# PI_DI_Input.net
KiCad netlist of a schematic drawn in Altium Designer
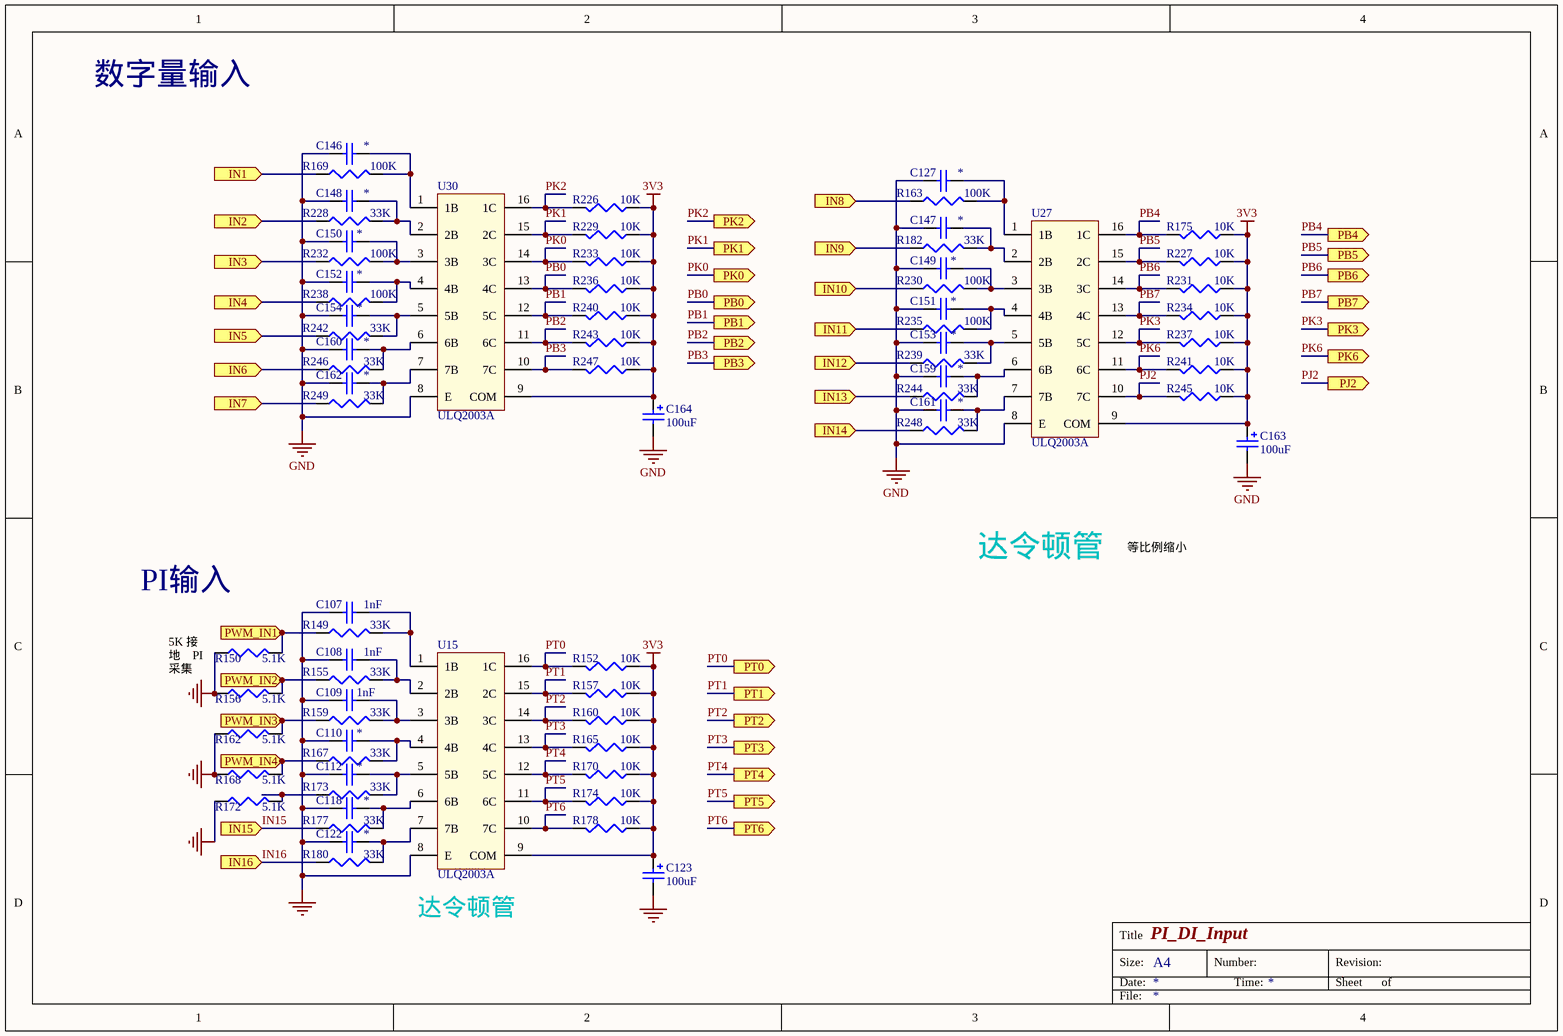
[diagram p0: PI_DI_Input.SchDoc]

(export (version "E")
  (design (tool "Eeschema 10.0.6"))
  (components
    (comp (ref "C107")
      (value "1nF")
      (footprint "0603-L")
      (description "Capacitor")
      (fields (field (name "Comment") "Cap") (field (name "PUBLISHER") "Altium Limited"))
      (libsource (lib "Miscellaneous Devices") (part "Cap"))
    )
    (comp (ref "C108")
      (value "1nF")
      (footprint "0603-L")
      (description "Capacitor")
      (fields (field (name "Comment") "Cap") (field (name "PUBLISHER") "Altium Limited"))
      (libsource (lib "Miscellaneous Devices") (part "Cap"))
    )
    (comp (ref "C109")
      (value "1nF")
      (footprint "0603-L")
      (description "Capacitor")
      (fields (field (name "Comment") "Cap") (field (name "PUBLISHER") "Altium Limited"))
      (libsource (lib "Miscellaneous Devices") (part "Cap"))
    )
    (comp (ref "C110")
      (value "Cap")
      (footprint "0603-L")
      (description "Capacitor")
      (fields (field (name "ALTIUM_VALUE") "*") (field (name "PUBLISHER") "Altium Limited"))
      (libsource (lib "Miscellaneous Devices") (part "Cap"))
    )
    (comp (ref "C112")
      (value "Cap")
      (footprint "0603-L")
      (description "Capacitor")
      (fields (field (name "ALTIUM_VALUE") "*") (field (name "PUBLISHER") "Altium Limited"))
      (libsource (lib "Miscellaneous Devices") (part "Cap"))
    )
    (comp (ref "C118")
      (value "Cap")
      (footprint "0603-L")
      (description "Capacitor")
      (fields (field (name "ALTIUM_VALUE") "*") (field (name "PUBLISHER") "Altium Limited"))
      (libsource (lib "Miscellaneous Devices") (part "Cap"))
    )
    (comp (ref "C122")
      (value "Cap")
      (footprint "0603-L")
      (description "Capacitor")
      (fields (field (name "ALTIUM_VALUE") "*") (field (name "PUBLISHER") "Altium Limited"))
      (libsource (lib "Miscellaneous Devices") (part "Cap"))
    )
    (comp (ref "C123")
      (value "100uF")
      (footprint "CAP1+")
      (description "Polarized Capacitor (Axial)")
      (fields (field (name "Comment") "Cap Pol2") (field (name "PUBLISHER") "Altium Limited"))
      (libsource (lib "Miscellaneous Devices") (part "Cap Pol2"))
    )
    (comp (ref "C127")
      (value "Cap")
      (footprint "0603-L")
      (description "Capacitor")
      (fields (field (name "ALTIUM_VALUE") "*") (field (name "PUBLISHER") "Altium Limited"))
      (libsource (lib "Miscellaneous Devices") (part "Cap"))
    )
    (comp (ref "C146")
      (value "Cap")
      (footprint "0603-L")
      (description "Capacitor")
      (fields (field (name "ALTIUM_VALUE") "*") (field (name "PUBLISHER") "Altium Limited"))
      (libsource (lib "Miscellaneous Devices") (part "Cap"))
    )
    (comp (ref "C147")
      (value "Cap")
      (footprint "0603-L")
      (description "Capacitor")
      (fields (field (name "ALTIUM_VALUE") "*") (field (name "PUBLISHER") "Altium Limited"))
      (libsource (lib "Miscellaneous Devices") (part "Cap"))
    )
    (comp (ref "C148")
      (value "Cap")
      (footprint "0603-L")
      (description "Capacitor")
      (fields (field (name "ALTIUM_VALUE") "*") (field (name "PUBLISHER") "Altium Limited"))
      (libsource (lib "Miscellaneous Devices") (part "Cap"))
    )
    (comp (ref "C149")
      (value "Cap")
      (footprint "0603-L")
      (description "Capacitor")
      (fields (field (name "ALTIUM_VALUE") "*") (field (name "PUBLISHER") "Altium Limited"))
      (libsource (lib "Miscellaneous Devices") (part "Cap"))
    )
    (comp (ref "C150")
      (value "Cap")
      (footprint "0603-L")
      (description "Capacitor")
      (fields (field (name "ALTIUM_VALUE") "*") (field (name "PUBLISHER") "Altium Limited"))
      (libsource (lib "Miscellaneous Devices") (part "Cap"))
    )
    (comp (ref "C151")
      (value "Cap")
      (footprint "0603-L")
      (description "Capacitor")
      (fields (field (name "ALTIUM_VALUE") "*") (field (name "PUBLISHER") "Altium Limited"))
      (libsource (lib "Miscellaneous Devices") (part "Cap"))
    )
    (comp (ref "C152")
      (value "Cap")
      (footprint "0603-L")
      (description "Capacitor")
      (fields (field (name "ALTIUM_VALUE") "*") (field (name "PUBLISHER") "Altium Limited"))
      (libsource (lib "Miscellaneous Devices") (part "Cap"))
    )
    (comp (ref "C153")
      (value "Cap")
      (footprint "0603-L")
      (description "Capacitor")
      (fields (field (name "ALTIUM_VALUE") "*") (field (name "PUBLISHER") "Altium Limited"))
      (libsource (lib "Miscellaneous Devices") (part "Cap"))
    )
    (comp (ref "C154")
      (value "Cap")
      (footprint "0603-L")
      (description "Capacitor")
      (fields (field (name "ALTIUM_VALUE") "*") (field (name "PUBLISHER") "Altium Limited"))
      (libsource (lib "Miscellaneous Devices") (part "Cap"))
    )
    (comp (ref "C159")
      (value "Cap")
      (footprint "0603-L")
      (description "Capacitor")
      (fields (field (name "ALTIUM_VALUE") "*") (field (name "PUBLISHER") "Altium Limited"))
      (libsource (lib "Miscellaneous Devices") (part "Cap"))
    )
    (comp (ref "C160")
      (value "Cap")
      (footprint "0603-L")
      (description "Capacitor")
      (fields (field (name "ALTIUM_VALUE") "*") (field (name "PUBLISHER") "Altium Limited"))
      (libsource (lib "Miscellaneous Devices") (part "Cap"))
    )
    (comp (ref "C161")
      (value "Cap")
      (footprint "0603-L")
      (description "Capacitor")
      (fields (field (name "ALTIUM_VALUE") "*") (field (name "PUBLISHER") "Altium Limited"))
      (libsource (lib "Miscellaneous Devices") (part "Cap"))
    )
    (comp (ref "C162")
      (value "Cap")
      (footprint "0603-L")
      (description "Capacitor")
      (fields (field (name "ALTIUM_VALUE") "*") (field (name "PUBLISHER") "Altium Limited"))
      (libsource (lib "Miscellaneous Devices") (part "Cap"))
    )
    (comp (ref "C163")
      (value "100uF")
      (footprint "CAP1+")
      (description "Polarized Capacitor (Axial)")
      (fields (field (name "Comment") "Cap Pol2") (field (name "PUBLISHER") "Altium Limited"))
      (libsource (lib "Miscellaneous Devices") (part "Cap Pol2"))
    )
    (comp (ref "C164")
      (value "100uF")
      (footprint "CAP1+")
      (description "Polarized Capacitor (Axial)")
      (fields (field (name "Comment") "Cap Pol2") (field (name "PUBLISHER") "Altium Limited"))
      (libsource (lib "Miscellaneous Devices") (part "Cap Pol2"))
    )
    (comp (ref "R149")
      (value "33K")
      (footprint "0603-L")
      (description "Resistor")
      (fields (field (name "Comment") "Res3") (field (name "PUBLISHER") "Altium Limited"))
      (libsource (lib "Miscellaneous Devices") (part "Res3"))
    )
    (comp (ref "R150")
      (value "5.1K")
      (footprint "0603-L")
      (description "Resistor")
      (fields (field (name "Comment") "Res3") (field (name "PUBLISHER") "Altium Limited"))
      (libsource (lib "Miscellaneous Devices") (part "Res3"))
    )
    (comp (ref "R152")
      (value "10K")
      (footprint "0603-L")
      (description "Resistor")
      (fields (field (name "Comment") "Res3") (field (name "PUBLISHER") "Altium Limited"))
      (libsource (lib "Miscellaneous Devices") (part "Res3"))
    )
    (comp (ref "R155")
      (value "33K")
      (footprint "0603-L")
      (description "Resistor")
      (fields (field (name "Comment") "Res3") (field (name "PUBLISHER") "Altium Limited"))
      (libsource (lib "Miscellaneous Devices") (part "Res3"))
    )
    (comp (ref "R156")
      (value "5.1K")
      (footprint "0603-L")
      (description "Resistor")
      (fields (field (name "Comment") "Res3") (field (name "PUBLISHER") "Altium Limited"))
      (libsource (lib "Miscellaneous Devices") (part "Res3"))
    )
    (comp (ref "R157")
      (value "10K")
      (footprint "0603-L")
      (description "Resistor")
      (fields (field (name "Comment") "Res3") (field (name "PUBLISHER") "Altium Limited"))
      (libsource (lib "Miscellaneous Devices") (part "Res3"))
    )
    (comp (ref "R159")
      (value "33K")
      (footprint "0603-L")
      (description "Resistor")
      (fields (field (name "Comment") "Res3") (field (name "PUBLISHER") "Altium Limited"))
      (libsource (lib "Miscellaneous Devices") (part "Res3"))
    )
    (comp (ref "R160")
      (value "10K")
      (footprint "0603-L")
      (description "Resistor")
      (fields (field (name "Comment") "Res3") (field (name "PUBLISHER") "Altium Limited"))
      (libsource (lib "Miscellaneous Devices") (part "Res3"))
    )
    (comp (ref "R162")
      (value "5.1K")
      (footprint "0603-L")
      (description "Resistor")
      (fields (field (name "Comment") "Res3") (field (name "PUBLISHER") "Altium Limited"))
      (libsource (lib "Miscellaneous Devices") (part "Res3"))
    )
    (comp (ref "R163")
      (value "100K")
      (footprint "0603-L")
      (description "Resistor")
      (fields (field (name "Comment") "Res3") (field (name "PUBLISHER") "Altium Limited"))
      (libsource (lib "Miscellaneous Devices") (part "Res3"))
    )
    (comp (ref "R165")
      (value "10K")
      (footprint "0603-L")
      (description "Resistor")
      (fields (field (name "Comment") "Res3") (field (name "PUBLISHER") "Altium Limited"))
      (libsource (lib "Miscellaneous Devices") (part "Res3"))
    )
    (comp (ref "R167")
      (value "33K")
      (footprint "0603-L")
      (description "Resistor")
      (fields (field (name "Comment") "Res3") (field (name "PUBLISHER") "Altium Limited"))
      (libsource (lib "Miscellaneous Devices") (part "Res3"))
    )
    (comp (ref "R168")
      (value "5.1K")
      (footprint "0603-L")
      (description "Resistor")
      (fields (field (name "Comment") "Res3") (field (name "PUBLISHER") "Altium Limited"))
      (libsource (lib "Miscellaneous Devices") (part "Res3"))
    )
    (comp (ref "R169")
      (value "100K")
      (footprint "0603-L")
      (description "Resistor")
      (fields (field (name "Comment") "Res3") (field (name "PUBLISHER") "Altium Limited"))
      (libsource (lib "Miscellaneous Devices") (part "Res3"))
    )
    (comp (ref "R170")
      (value "10K")
      (footprint "0603-L")
      (description "Resistor")
      (fields (field (name "Comment") "Res3") (field (name "PUBLISHER") "Altium Limited"))
      (libsource (lib "Miscellaneous Devices") (part "Res3"))
    )
    (comp (ref "R172")
      (value "5.1K")
      (footprint "0603-L")
      (description "Resistor")
      (fields (field (name "Comment") "Res3") (field (name "PUBLISHER") "Altium Limited"))
      (libsource (lib "Miscellaneous Devices") (part "Res3"))
    )
    (comp (ref "R173")
      (value "33K")
      (footprint "0603-L")
      (description "Resistor")
      (fields (field (name "Comment") "Res3") (field (name "PUBLISHER") "Altium Limited"))
      (libsource (lib "Miscellaneous Devices") (part "Res3"))
    )
    (comp (ref "R174")
      (value "10K")
      (footprint "0603-L")
      (description "Resistor")
      (fields (field (name "Comment") "Res3") (field (name "PUBLISHER") "Altium Limited"))
      (libsource (lib "Miscellaneous Devices") (part "Res3"))
    )
    (comp (ref "R175")
      (value "10K")
      (footprint "0603-L")
      (description "Resistor")
      (fields (field (name "Comment") "Res3") (field (name "PUBLISHER") "Altium Limited"))
      (libsource (lib "Miscellaneous Devices") (part "Res3"))
    )
    (comp (ref "R177")
      (value "33K")
      (footprint "0603-L")
      (description "Resistor")
      (fields (field (name "Comment") "Res3") (field (name "PUBLISHER") "Altium Limited"))
      (libsource (lib "Miscellaneous Devices") (part "Res3"))
    )
    (comp (ref "R178")
      (value "10K")
      (footprint "0603-L")
      (description "Resistor")
      (fields (field (name "Comment") "Res3") (field (name "PUBLISHER") "Altium Limited"))
      (libsource (lib "Miscellaneous Devices") (part "Res3"))
    )
    (comp (ref "R180")
      (value "33K")
      (footprint "0603-L")
      (description "Resistor")
      (fields (field (name "Comment") "Res3") (field (name "PUBLISHER") "Altium Limited"))
      (libsource (lib "Miscellaneous Devices") (part "Res3"))
    )
    (comp (ref "R182")
      (value "33K")
      (footprint "0603-L")
      (description "Resistor")
      (fields (field (name "Comment") "Res3") (field (name "PUBLISHER") "Altium Limited"))
      (libsource (lib "Miscellaneous Devices") (part "Res3"))
    )
    (comp (ref "R226")
      (value "10K")
      (footprint "0603-L")
      (description "Resistor")
      (fields (field (name "Comment") "Res3") (field (name "PUBLISHER") "Altium Limited"))
      (libsource (lib "Miscellaneous Devices") (part "Res3"))
    )
    (comp (ref "R227")
      (value "10K")
      (footprint "0603-L")
      (description "Resistor")
      (fields (field (name "Comment") "Res3") (field (name "PUBLISHER") "Altium Limited"))
      (libsource (lib "Miscellaneous Devices") (part "Res3"))
    )
    (comp (ref "R228")
      (value "33K")
      (footprint "0603-L")
      (description "Resistor")
      (fields (field (name "Comment") "Res3") (field (name "PUBLISHER") "Altium Limited"))
      (libsource (lib "Miscellaneous Devices") (part "Res3"))
    )
    (comp (ref "R229")
      (value "10K")
      (footprint "0603-L")
      (description "Resistor")
      (fields (field (name "Comment") "Res3") (field (name "PUBLISHER") "Altium Limited"))
      (libsource (lib "Miscellaneous Devices") (part "Res3"))
    )
    (comp (ref "R230")
      (value "100K")
      (footprint "0603-L")
      (description "Resistor")
      (fields (field (name "Comment") "Res3") (field (name "PUBLISHER") "Altium Limited"))
      (libsource (lib "Miscellaneous Devices") (part "Res3"))
    )
    (comp (ref "R231")
      (value "10K")
      (footprint "0603-L")
      (description "Resistor")
      (fields (field (name "Comment") "Res3") (field (name "PUBLISHER") "Altium Limited"))
      (libsource (lib "Miscellaneous Devices") (part "Res3"))
    )
    (comp (ref "R232")
      (value "100K")
      (footprint "0603-L")
      (description "Resistor")
      (fields (field (name "Comment") "Res3") (field (name "PUBLISHER") "Altium Limited"))
      (libsource (lib "Miscellaneous Devices") (part "Res3"))
    )
    (comp (ref "R233")
      (value "10K")
      (footprint "0603-L")
      (description "Resistor")
      (fields (field (name "Comment") "Res3") (field (name "PUBLISHER") "Altium Limited"))
      (libsource (lib "Miscellaneous Devices") (part "Res3"))
    )
    (comp (ref "R234")
      (value "10K")
      (footprint "0603-L")
      (description "Resistor")
      (fields (field (name "Comment") "Res3") (field (name "PUBLISHER") "Altium Limited"))
      (libsource (lib "Miscellaneous Devices") (part "Res3"))
    )
    (comp (ref "R235")
      (value "100K")
      (footprint "0603-L")
      (description "Resistor")
      (fields (field (name "Comment") "Res3") (field (name "PUBLISHER") "Altium Limited"))
      (libsource (lib "Miscellaneous Devices") (part "Res3"))
    )
    (comp (ref "R236")
      (value "10K")
      (footprint "0603-L")
      (description "Resistor")
      (fields (field (name "Comment") "Res3") (field (name "PUBLISHER") "Altium Limited"))
      (libsource (lib "Miscellaneous Devices") (part "Res3"))
    )
    (comp (ref "R237")
      (value "10K")
      (footprint "0603-L")
      (description "Resistor")
      (fields (field (name "Comment") "Res3") (field (name "PUBLISHER") "Altium Limited"))
      (libsource (lib "Miscellaneous Devices") (part "Res3"))
    )
    (comp (ref "R238")
      (value "100K")
      (footprint "0603-L")
      (description "Resistor")
      (fields (field (name "Comment") "Res3") (field (name "PUBLISHER") "Altium Limited"))
      (libsource (lib "Miscellaneous Devices") (part "Res3"))
    )
    (comp (ref "R239")
      (value "33K")
      (footprint "0603-L")
      (description "Resistor")
      (fields (field (name "Comment") "Res3") (field (name "PUBLISHER") "Altium Limited"))
      (libsource (lib "Miscellaneous Devices") (part "Res3"))
    )
    (comp (ref "R240")
      (value "10K")
      (footprint "0603-L")
      (description "Resistor")
      (fields (field (name "Comment") "Res3") (field (name "PUBLISHER") "Altium Limited"))
      (libsource (lib "Miscellaneous Devices") (part "Res3"))
    )
    (comp (ref "R241")
      (value "10K")
      (footprint "0603-L")
      (description "Resistor")
      (fields (field (name "Comment") "Res3") (field (name "PUBLISHER") "Altium Limited"))
      (libsource (lib "Miscellaneous Devices") (part "Res3"))
    )
    (comp (ref "R242")
      (value "33K")
      (footprint "0603-L")
      (description "Resistor")
      (fields (field (name "Comment") "Res3") (field (name "PUBLISHER") "Altium Limited"))
      (libsource (lib "Miscellaneous Devices") (part "Res3"))
    )
    (comp (ref "R243")
      (value "10K")
      (footprint "0603-L")
      (description "Resistor")
      (fields (field (name "Comment") "Res3") (field (name "PUBLISHER") "Altium Limited"))
      (libsource (lib "Miscellaneous Devices") (part "Res3"))
    )
    (comp (ref "R244")
      (value "33K")
      (footprint "0603-L")
      (description "Resistor")
      (fields (field (name "Comment") "Res3") (field (name "PUBLISHER") "Altium Limited"))
      (libsource (lib "Miscellaneous Devices") (part "Res3"))
    )
    (comp (ref "R245")
      (value "10K")
      (footprint "0603-L")
      (description "Resistor")
      (fields (field (name "Comment") "Res3") (field (name "PUBLISHER") "Altium Limited"))
      (libsource (lib "Miscellaneous Devices") (part "Res3"))
    )
    (comp (ref "R246")
      (value "33K")
      (footprint "0603-L")
      (description "Resistor")
      (fields (field (name "Comment") "Res3") (field (name "PUBLISHER") "Altium Limited"))
      (libsource (lib "Miscellaneous Devices") (part "Res3"))
    )
    (comp (ref "R247")
      (value "10K")
      (footprint "0603-L")
      (description "Resistor")
      (fields (field (name "Comment") "Res3") (field (name "PUBLISHER") "Altium Limited"))
      (libsource (lib "Miscellaneous Devices") (part "Res3"))
    )
    (comp (ref "R248")
      (value "33K")
      (footprint "0603-L")
      (description "Resistor")
      (fields (field (name "Comment") "Res3") (field (name "PUBLISHER") "Altium Limited"))
      (libsource (lib "Miscellaneous Devices") (part "Res3"))
    )
    (comp (ref "R249")
      (value "33K")
      (footprint "0603-L")
      (description "Resistor")
      (fields (field (name "Comment") "Res3") (field (name "PUBLISHER") "Altium Limited"))
      (libsource (lib "Miscellaneous Devices") (part "Res3"))
    )
    (comp (ref "U15") (value "ULQ2003A") (footprint "HC4851") (libsource (lib "整车控制器") (part "ULQ2003A")))
    (comp (ref "U27") (value "ULQ2003A") (footprint "HC4851") (libsource (lib "整车控制器") (part "ULQ2003A")))
    (comp (ref "U30") (value "ULQ2003A") (footprint "HC4851") (libsource (lib "整车控制器") (part "ULQ2003A")))
  )
  (nets
    (net (code "1") (name "/IN1") (class "Default")
      (node (ref "R169") (pin "1") (pinfunction "1_1") (pintype "passive"))
    )
    (net (code "2") (name "/IN2") (class "Default")
      (node (ref "R228") (pin "1") (pinfunction "1_1") (pintype "passive"))
    )
    (net (code "3") (name "/IN3") (class "Default")
      (node (ref "R232") (pin "1") (pinfunction "1_1") (pintype "passive"))
    )
    (net (code "4") (name "/IN4") (class "Default")
      (node (ref "R238") (pin "1") (pinfunction "1_1") (pintype "passive"))
    )
    (net (code "5") (name "/IN5") (class "Default")
      (node (ref "R242") (pin "1") (pinfunction "1_1") (pintype "passive"))
    )
    (net (code "6") (name "/IN6") (class "Default")
      (node (ref "R246") (pin "1") (pinfunction "1_1") (pintype "passive"))
    )
    (net (code "7") (name "/IN7") (class "Default")
      (node (ref "R249") (pin "1") (pinfunction "1_1") (pintype "passive"))
    )
    (net (code "8") (name "/IN8") (class "Default")
      (node (ref "R163") (pin "1") (pinfunction "1_1") (pintype "passive"))
    )
    (net (code "9") (name "/IN9") (class "Default")
      (node (ref "R182") (pin "1") (pinfunction "1_1") (pintype "passive"))
    )
    (net (code "10") (name "/IN10") (class "Default")
      (node (ref "R230") (pin "1") (pinfunction "1_1") (pintype "passive"))
    )
    (net (code "11") (name "/IN11") (class "Default")
      (node (ref "R235") (pin "1") (pinfunction "1_1") (pintype "passive"))
    )
    (net (code "12") (name "/IN12") (class "Default")
      (node (ref "R239") (pin "1") (pinfunction "1_1") (pintype "passive"))
    )
    (net (code "13") (name "/IN13") (class "Default")
      (node (ref "R244") (pin "1") (pinfunction "1_1") (pintype "passive"))
    )
    (net (code "14") (name "/IN14") (class "Default")
      (node (ref "R248") (pin "1") (pinfunction "1_1") (pintype "passive"))
    )
    (net (code "15") (name "/IN15") (class "Default")
      (node (ref "R177") (pin "1") (pinfunction "1_1") (pintype "passive"))
    )
    (net (code "16") (name "/IN16") (class "Default")
      (node (ref "R180") (pin "1") (pinfunction "1_1") (pintype "passive"))
    )
    (net (code "17") (name "/PB0") (class "Default")
      (node (ref "R236") (pin "2") (pinfunction "2_2") (pintype "passive"))
      (node (ref "U30") (pin "13") (pinfunction "4C_13") (pintype "passive"))
    )
    (net (code "18") (name "/PB1") (class "Default")
      (node (ref "R240") (pin "2") (pinfunction "2_2") (pintype "passive"))
      (node (ref "U30") (pin "12") (pinfunction "5C_12") (pintype "passive"))
    )
    (net (code "19") (name "/PB2") (class "Default")
      (node (ref "R243") (pin "2") (pinfunction "2_2") (pintype "passive"))
      (node (ref "U30") (pin "11") (pinfunction "6C_11") (pintype "passive"))
    )
    (net (code "20") (name "/PB3") (class "Default")
      (node (ref "R247") (pin "2") (pinfunction "2_2") (pintype "passive"))
      (node (ref "U30") (pin "10") (pinfunction "7C_10") (pintype "passive"))
    )
    (net (code "21") (name "/PB4") (class "Default")
      (node (ref "R175") (pin "2") (pinfunction "2_2") (pintype "passive"))
      (node (ref "U27") (pin "16") (pinfunction "1C_16") (pintype "passive"))
    )
    (net (code "22") (name "/PB5") (class "Default")
      (node (ref "R227") (pin "2") (pinfunction "2_2") (pintype "passive"))
      (node (ref "U27") (pin "15") (pinfunction "2C_15") (pintype "passive"))
    )
    (net (code "23") (name "/PB6") (class "Default")
      (node (ref "R231") (pin "2") (pinfunction "2_2") (pintype "passive"))
      (node (ref "U27") (pin "14") (pinfunction "3C_14") (pintype "passive"))
    )
    (net (code "24") (name "/PB7") (class "Default")
      (node (ref "R234") (pin "2") (pinfunction "2_2") (pintype "passive"))
      (node (ref "U27") (pin "13") (pinfunction "4C_13") (pintype "passive"))
    )
    (net (code "25") (name "/PJ2") (class "Default")
      (node (ref "R245") (pin "2") (pinfunction "2_2") (pintype "passive"))
      (node (ref "U27") (pin "10") (pinfunction "7C_10") (pintype "passive"))
    )
    (net (code "26") (name "/PK0") (class "Default")
      (node (ref "R233") (pin "2") (pinfunction "2_2") (pintype "passive"))
      (node (ref "U30") (pin "14") (pinfunction "3C_14") (pintype "passive"))
    )
    (net (code "27") (name "/PK1") (class "Default")
      (node (ref "R229") (pin "2") (pinfunction "2_2") (pintype "passive"))
      (node (ref "U30") (pin "15") (pinfunction "2C_15") (pintype "passive"))
    )
    (net (code "28") (name "/PK2") (class "Default")
      (node (ref "R226") (pin "2") (pinfunction "2_2") (pintype "passive"))
      (node (ref "U30") (pin "16") (pinfunction "1C_16") (pintype "passive"))
    )
    (net (code "29") (name "/PK3") (class "Default")
      (node (ref "R237") (pin "2") (pinfunction "2_2") (pintype "passive"))
      (node (ref "U27") (pin "12") (pinfunction "5C_12") (pintype "passive"))
    )
    (net (code "30") (name "/PK6") (class "Default")
      (node (ref "R241") (pin "2") (pinfunction "2_2") (pintype "passive"))
      (node (ref "U27") (pin "11") (pinfunction "6C_11") (pintype "passive"))
    )
    (net (code "31") (name "/PT0") (class "Default")
      (node (ref "R152") (pin "2") (pinfunction "2_2") (pintype "passive"))
      (node (ref "U15") (pin "16") (pinfunction "1C_16") (pintype "passive"))
    )
    (net (code "32") (name "/PT1") (class "Default")
      (node (ref "R157") (pin "2") (pinfunction "2_2") (pintype "passive"))
      (node (ref "U15") (pin "15") (pinfunction "2C_15") (pintype "passive"))
    )
    (net (code "33") (name "/PT2") (class "Default")
      (node (ref "R160") (pin "2") (pinfunction "2_2") (pintype "passive"))
      (node (ref "U15") (pin "14") (pinfunction "3C_14") (pintype "passive"))
    )
    (net (code "34") (name "/PT3") (class "Default")
      (node (ref "R165") (pin "2") (pinfunction "2_2") (pintype "passive"))
      (node (ref "U15") (pin "13") (pinfunction "4C_13") (pintype "passive"))
    )
    (net (code "35") (name "/PT4") (class "Default")
      (node (ref "R170") (pin "2") (pinfunction "2_2") (pintype "passive"))
      (node (ref "U15") (pin "12") (pinfunction "5C_12") (pintype "passive"))
    )
    (net (code "36") (name "/PT5") (class "Default")
      (node (ref "R174") (pin "2") (pinfunction "2_2") (pintype "passive"))
      (node (ref "U15") (pin "11") (pinfunction "6C_11") (pintype "passive"))
    )
    (net (code "37") (name "/PT6") (class "Default")
      (node (ref "R178") (pin "2") (pinfunction "2_2") (pintype "passive"))
      (node (ref "U15") (pin "10") (pinfunction "7C_10") (pintype "passive"))
    )
    (net (code "38") (name "/PWM_IN1") (class "Default")
      (node (ref "R149") (pin "1") (pinfunction "1_1") (pintype "passive"))
      (node (ref "R150") (pin "2") (pinfunction "2_2") (pintype "passive"))
    )
    (net (code "39") (name "/PWM_IN2") (class "Default")
      (node (ref "R155") (pin "1") (pinfunction "1_1") (pintype "passive"))
      (node (ref "R156") (pin "2") (pinfunction "2_2") (pintype "passive"))
    )
    (net (code "40") (name "/PWM_IN3") (class "Default")
      (node (ref "R159") (pin "1") (pinfunction "1_1") (pintype "passive"))
      (node (ref "R162") (pin "2") (pinfunction "2_2") (pintype "passive"))
    )
    (net (code "41") (name "/PWM_IN4") (class "Default")
      (node (ref "R167") (pin "1") (pinfunction "1_1") (pintype "passive"))
      (node (ref "R168") (pin "2") (pinfunction "2_2") (pintype "passive"))
    )
    (net (code "42") (name "3V3") (class "Default")
      (node (ref "C123") (pin "1") (pinfunction "1_1") (pintype "passive"))
      (node (ref "C163") (pin "1") (pinfunction "1_1") (pintype "passive"))
      (node (ref "C164") (pin "1") (pinfunction "1_1") (pintype "passive"))
      (node (ref "R152") (pin "1") (pinfunction "1_1") (pintype "passive"))
      (node (ref "R157") (pin "1") (pinfunction "1_1") (pintype "passive"))
      (node (ref "R160") (pin "1") (pinfunction "1_1") (pintype "passive"))
      (node (ref "R165") (pin "1") (pinfunction "1_1") (pintype "passive"))
      (node (ref "R170") (pin "1") (pinfunction "1_1") (pintype "passive"))
      (node (ref "R174") (pin "1") (pinfunction "1_1") (pintype "passive"))
      (node (ref "R175") (pin "1") (pinfunction "1_1") (pintype "passive"))
      (node (ref "R178") (pin "1") (pinfunction "1_1") (pintype "passive"))
      (node (ref "R226") (pin "1") (pinfunction "1_1") (pintype "passive"))
      (node (ref "R227") (pin "1") (pinfunction "1_1") (pintype "passive"))
      (node (ref "R229") (pin "1") (pinfunction "1_1") (pintype "passive"))
      (node (ref "R231") (pin "1") (pinfunction "1_1") (pintype "passive"))
      (node (ref "R233") (pin "1") (pinfunction "1_1") (pintype "passive"))
      (node (ref "R234") (pin "1") (pinfunction "1_1") (pintype "passive"))
      (node (ref "R236") (pin "1") (pinfunction "1_1") (pintype "passive"))
      (node (ref "R237") (pin "1") (pinfunction "1_1") (pintype "passive"))
      (node (ref "R240") (pin "1") (pinfunction "1_1") (pintype "passive"))
      (node (ref "R241") (pin "1") (pinfunction "1_1") (pintype "passive"))
      (node (ref "R243") (pin "1") (pinfunction "1_1") (pintype "passive"))
      (node (ref "R245") (pin "1") (pinfunction "1_1") (pintype "passive"))
      (node (ref "R247") (pin "1") (pinfunction "1_1") (pintype "passive"))
      (node (ref "U15") (pin "9") (pinfunction "COM_9") (pintype "passive"))
      (node (ref "U27") (pin "9") (pinfunction "COM_9") (pintype "passive"))
      (node (ref "U30") (pin "9") (pinfunction "COM_9") (pintype "passive"))
    )
    (net (code "43") (name "GND") (class "Default")
      (node (ref "C107") (pin "2") (pinfunction "2_2") (pintype "passive"))
      (node (ref "C108") (pin "2") (pinfunction "2_2") (pintype "passive"))
      (node (ref "C109") (pin "2") (pinfunction "2_2") (pintype "passive"))
      (node (ref "C110") (pin "2") (pinfunction "2_2") (pintype "passive"))
      (node (ref "C112") (pin "2") (pinfunction "2_2") (pintype "passive"))
      (node (ref "C118") (pin "2") (pinfunction "2_2") (pintype "passive"))
      (node (ref "C122") (pin "2") (pinfunction "2_2") (pintype "passive"))
      (node (ref "C123") (pin "2") (pinfunction "2_2") (pintype "passive"))
      (node (ref "C127") (pin "2") (pinfunction "2_2") (pintype "passive"))
      (node (ref "C146") (pin "2") (pinfunction "2_2") (pintype "passive"))
      (node (ref "C147") (pin "2") (pinfunction "2_2") (pintype "passive"))
      (node (ref "C148") (pin "2") (pinfunction "2_2") (pintype "passive"))
      (node (ref "C149") (pin "2") (pinfunction "2_2") (pintype "passive"))
      (node (ref "C150") (pin "2") (pinfunction "2_2") (pintype "passive"))
      (node (ref "C151") (pin "2") (pinfunction "2_2") (pintype "passive"))
      (node (ref "C152") (pin "2") (pinfunction "2_2") (pintype "passive"))
      (node (ref "C153") (pin "2") (pinfunction "2_2") (pintype "passive"))
      (node (ref "C154") (pin "2") (pinfunction "2_2") (pintype "passive"))
      (node (ref "C159") (pin "2") (pinfunction "2_2") (pintype "passive"))
      (node (ref "C160") (pin "2") (pinfunction "2_2") (pintype "passive"))
      (node (ref "C161") (pin "2") (pinfunction "2_2") (pintype "passive"))
      (node (ref "C162") (pin "2") (pinfunction "2_2") (pintype "passive"))
      (node (ref "C163") (pin "2") (pinfunction "2_2") (pintype "passive"))
      (node (ref "C164") (pin "2") (pinfunction "2_2") (pintype "passive"))
      (node (ref "R150") (pin "1") (pinfunction "1_1") (pintype "passive"))
      (node (ref "R156") (pin "1") (pinfunction "1_1") (pintype "passive"))
      (node (ref "R162") (pin "1") (pinfunction "1_1") (pintype "passive"))
      (node (ref "R168") (pin "1") (pinfunction "1_1") (pintype "passive"))
      (node (ref "R172") (pin "1") (pinfunction "1_1") (pintype "passive"))
      (node (ref "U15") (pin "8") (pinfunction "E_8") (pintype "passive"))
      (node (ref "U27") (pin "8") (pinfunction "E_8") (pintype "passive"))
      (node (ref "U30") (pin "8") (pinfunction "E_8") (pintype "passive"))
    )
    (net (code "44") (name "Net-(R172-Pad2)") (class "Default")
      (node (ref "R172") (pin "2") (pinfunction "2_2") (pintype "passive"))
      (node (ref "R173") (pin "1") (pinfunction "1_1") (pintype "passive"))
    )
    (net (code "45") (name "Net-(U15-1B)") (class "Default")
      (node (ref "C107") (pin "1") (pinfunction "1_1") (pintype "passive"))
      (node (ref "R149") (pin "2") (pinfunction "2_2") (pintype "passive"))
      (node (ref "U15") (pin "1") (pinfunction "1B_1") (pintype "passive"))
    )
    (net (code "46") (name "Net-(U15-2B)") (class "Default")
      (node (ref "C108") (pin "1") (pinfunction "1_1") (pintype "passive"))
      (node (ref "R155") (pin "2") (pinfunction "2_2") (pintype "passive"))
      (node (ref "U15") (pin "2") (pinfunction "2B_2") (pintype "passive"))
    )
    (net (code "47") (name "Net-(U15-3B)") (class "Default")
      (node (ref "C109") (pin "1") (pinfunction "1_1") (pintype "passive"))
      (node (ref "R159") (pin "2") (pinfunction "2_2") (pintype "passive"))
      (node (ref "U15") (pin "3") (pinfunction "3B_3") (pintype "passive"))
    )
    (net (code "48") (name "Net-(U15-4B)") (class "Default")
      (node (ref "C110") (pin "1") (pinfunction "1_1") (pintype "passive"))
      (node (ref "R167") (pin "2") (pinfunction "2_2") (pintype "passive"))
      (node (ref "U15") (pin "4") (pinfunction "4B_4") (pintype "passive"))
    )
    (net (code "49") (name "Net-(U15-5B)") (class "Default")
      (node (ref "C112") (pin "1") (pinfunction "1_1") (pintype "passive"))
      (node (ref "R173") (pin "2") (pinfunction "2_2") (pintype "passive"))
      (node (ref "U15") (pin "5") (pinfunction "5B_5") (pintype "passive"))
    )
    (net (code "50") (name "Net-(U15-6B)") (class "Default")
      (node (ref "C118") (pin "1") (pinfunction "1_1") (pintype "passive"))
      (node (ref "R177") (pin "2") (pinfunction "2_2") (pintype "passive"))
      (node (ref "U15") (pin "6") (pinfunction "6B_6") (pintype "passive"))
    )
    (net (code "51") (name "Net-(U15-7B)") (class "Default")
      (node (ref "C122") (pin "1") (pinfunction "1_1") (pintype "passive"))
      (node (ref "R180") (pin "2") (pinfunction "2_2") (pintype "passive"))
      (node (ref "U15") (pin "7") (pinfunction "7B_7") (pintype "passive"))
    )
    (net (code "52") (name "Net-(U27-1B)") (class "Default")
      (node (ref "C127") (pin "1") (pinfunction "1_1") (pintype "passive"))
      (node (ref "R163") (pin "2") (pinfunction "2_2") (pintype "passive"))
      (node (ref "U27") (pin "1") (pinfunction "1B_1") (pintype "passive"))
    )
    (net (code "53") (name "Net-(U27-2B)") (class "Default")
      (node (ref "C147") (pin "1") (pinfunction "1_1") (pintype "passive"))
      (node (ref "R182") (pin "2") (pinfunction "2_2") (pintype "passive"))
      (node (ref "U27") (pin "2") (pinfunction "2B_2") (pintype "passive"))
    )
    (net (code "54") (name "Net-(U27-3B)") (class "Default")
      (node (ref "C149") (pin "1") (pinfunction "1_1") (pintype "passive"))
      (node (ref "R230") (pin "2") (pinfunction "2_2") (pintype "passive"))
      (node (ref "U27") (pin "3") (pinfunction "3B_3") (pintype "passive"))
    )
    (net (code "55") (name "Net-(U27-4B)") (class "Default")
      (node (ref "C151") (pin "1") (pinfunction "1_1") (pintype "passive"))
      (node (ref "R235") (pin "2") (pinfunction "2_2") (pintype "passive"))
      (node (ref "U27") (pin "4") (pinfunction "4B_4") (pintype "passive"))
    )
    (net (code "56") (name "Net-(U27-5B)") (class "Default")
      (node (ref "C153") (pin "1") (pinfunction "1_1") (pintype "passive"))
      (node (ref "R239") (pin "2") (pinfunction "2_2") (pintype "passive"))
      (node (ref "U27") (pin "5") (pinfunction "5B_5") (pintype "passive"))
    )
    (net (code "57") (name "Net-(U27-6B)") (class "Default")
      (node (ref "C159") (pin "1") (pinfunction "1_1") (pintype "passive"))
      (node (ref "R244") (pin "2") (pinfunction "2_2") (pintype "passive"))
      (node (ref "U27") (pin "6") (pinfunction "6B_6") (pintype "passive"))
    )
    (net (code "58") (name "Net-(U27-7B)") (class "Default")
      (node (ref "C161") (pin "1") (pinfunction "1_1") (pintype "passive"))
      (node (ref "R248") (pin "2") (pinfunction "2_2") (pintype "passive"))
      (node (ref "U27") (pin "7") (pinfunction "7B_7") (pintype "passive"))
    )
    (net (code "59") (name "Net-(U30-1B)") (class "Default")
      (node (ref "C146") (pin "1") (pinfunction "1_1") (pintype "passive"))
      (node (ref "R169") (pin "2") (pinfunction "2_2") (pintype "passive"))
      (node (ref "U30") (pin "1") (pinfunction "1B_1") (pintype "passive"))
    )
    (net (code "60") (name "Net-(U30-2B)") (class "Default")
      (node (ref "C148") (pin "1") (pinfunction "1_1") (pintype "passive"))
      (node (ref "R228") (pin "2") (pinfunction "2_2") (pintype "passive"))
      (node (ref "U30") (pin "2") (pinfunction "2B_2") (pintype "passive"))
    )
    (net (code "61") (name "Net-(U30-3B)") (class "Default")
      (node (ref "C150") (pin "1") (pinfunction "1_1") (pintype "passive"))
      (node (ref "R232") (pin "2") (pinfunction "2_2") (pintype "passive"))
      (node (ref "U30") (pin "3") (pinfunction "3B_3") (pintype "passive"))
    )
    (net (code "62") (name "Net-(U30-4B)") (class "Default")
      (node (ref "C152") (pin "1") (pinfunction "1_1") (pintype "passive"))
      (node (ref "R238") (pin "2") (pinfunction "2_2") (pintype "passive"))
      (node (ref "U30") (pin "4") (pinfunction "4B_4") (pintype "passive"))
    )
    (net (code "63") (name "Net-(U30-5B)") (class "Default")
      (node (ref "C154") (pin "1") (pinfunction "1_1") (pintype "passive"))
      (node (ref "R242") (pin "2") (pinfunction "2_2") (pintype "passive"))
      (node (ref "U30") (pin "5") (pinfunction "5B_5") (pintype "passive"))
    )
    (net (code "64") (name "Net-(U30-6B)") (class "Default")
      (node (ref "C160") (pin "1") (pinfunction "1_1") (pintype "passive"))
      (node (ref "R246") (pin "2") (pinfunction "2_2") (pintype "passive"))
      (node (ref "U30") (pin "6") (pinfunction "6B_6") (pintype "passive"))
    )
    (net (code "65") (name "Net-(U30-7B)") (class "Default")
      (node (ref "C162") (pin "1") (pinfunction "1_1") (pintype "passive"))
      (node (ref "R249") (pin "2") (pinfunction "2_2") (pintype "passive"))
      (node (ref "U30") (pin "7") (pinfunction "7B_7") (pintype "passive"))
    )
  )
)
